# Zio_Qwiic_Gesture_Sensor_PAJ7620U2.net
KiCad netlist of a schematic drawn in EAGLE
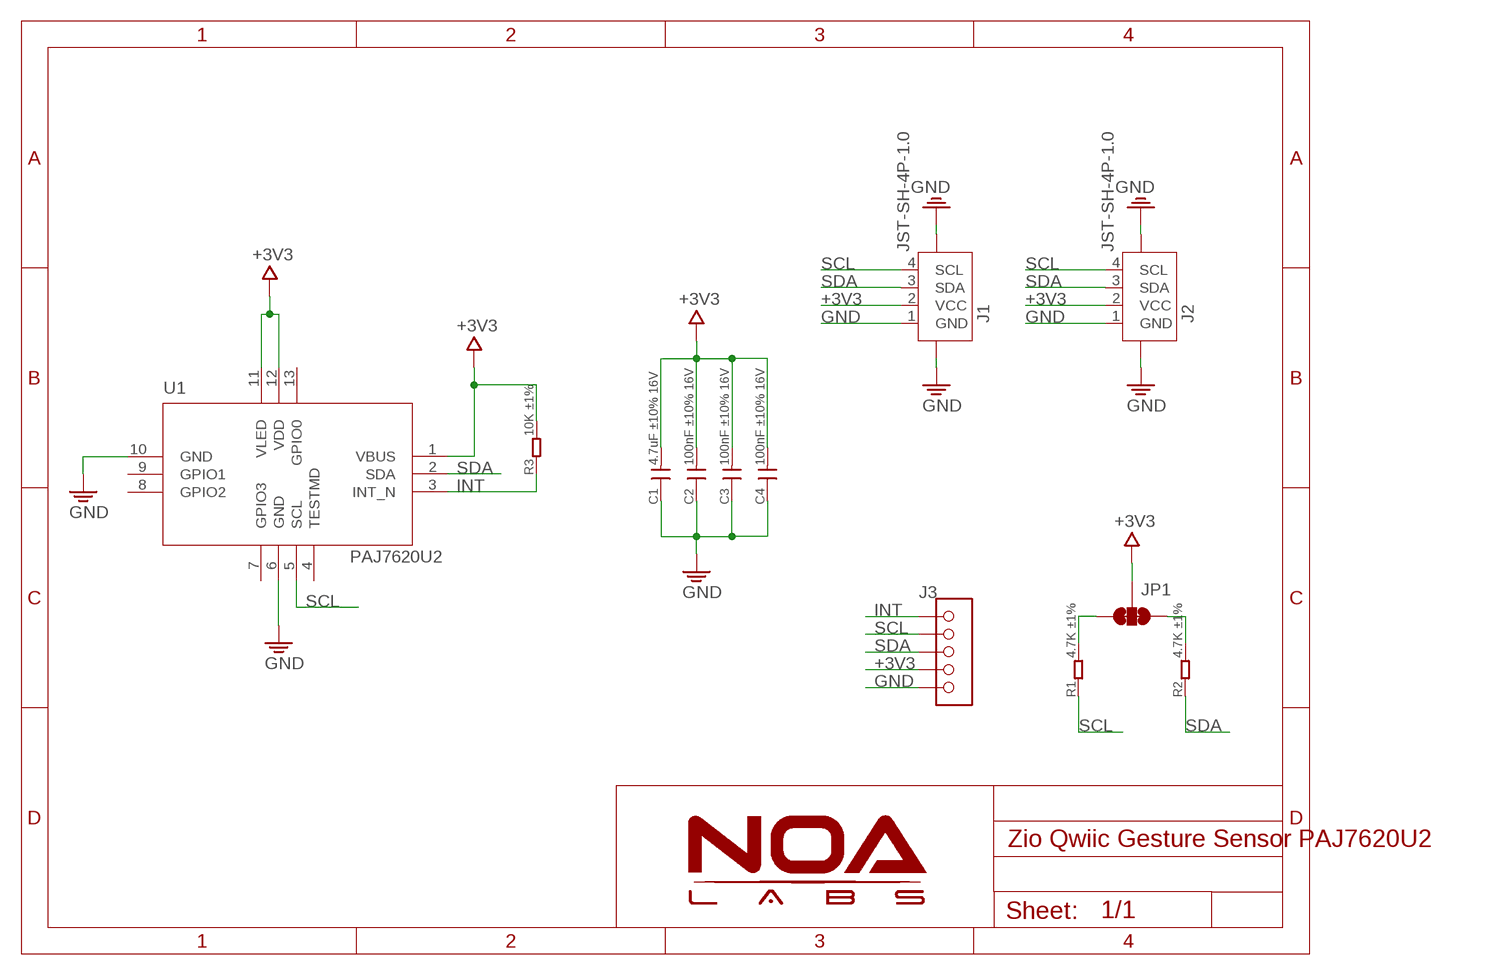
[diagram p0: schematic, sheet 1]

(export (version "E")
  (design (tool "Eeschema 10.0.6"))
  (components
    (comp (ref "C1")
      (value "4.7uF ±10% 16V")
      (footprint "eagle-import:C0603")
      (libsource (lib "eagle-import") (part "C-0603"))
    )
    (comp (ref "C2")
      (value "100nF ±10% 16V")
      (footprint "eagle-import:C0603")
      (libsource (lib "eagle-import") (part "C-0603"))
    )
    (comp (ref "C3")
      (value "100nF ±10% 16V")
      (footprint "eagle-import:C0603")
      (libsource (lib "eagle-import") (part "C-0603"))
    )
    (comp (ref "C4")
      (value "100nF ±10% 16V")
      (footprint "eagle-import:C0603")
      (libsource (lib "eagle-import") (part "C-0603"))
    )
    (comp (ref "J1")
      (value "JST-SH-4P-1.0")
      (footprint "eagle-import:JST-SH-4P")
      (libsource (lib "eagle-import") (part "JST-SH-4P-1.0"))
    )
    (comp (ref "J2")
      (value "JST-SH-4P-1.0")
      (footprint "eagle-import:JST-SH-4P")
      (libsource (lib "eagle-import") (part "JST-SH-4P-1.0"))
    )
    (comp (ref "J3")
      (value "HEADER-5P-2.54")
      (footprint "eagle-import:5P-2.54")
      (libsource (lib "eagle-import") (part "HEADER-5P-2.54"))
    )
    (comp (ref "JP1")
      (value "SMT-JUMPER_3_2-NC_TRACE")
      (footprint "eagle-import:SMT-JUMPER_3_2-NC_TRACE")
      (libsource (lib "eagle-import") (part "SMT-JUMPER_3_2-NC_TRACE"))
    )
    (comp (ref "R1")
      (value "4.7K ±1%")
      (footprint "eagle-import:R0603")
      (libsource (lib "eagle-import") (part "R-0603"))
    )
    (comp (ref "R2")
      (value "4.7K ±1%")
      (footprint "eagle-import:R0603")
      (libsource (lib "eagle-import") (part "R-0603"))
    )
    (comp (ref "R3")
      (value "10K ±1%")
      (footprint "eagle-import:R0603")
      (libsource (lib "eagle-import") (part "R-0603"))
    )
    (comp (ref "U1")
      (value "PAJ7620U2")
      (footprint "eagle-import:PAJ7620U2")
      (libsource (lib "eagle-import") (part "PAJ7620U2"))
    )
  )
  (nets
    (net (code "1") (name "+3V3") (class "Default")
      (node (ref "C1") (pin "2") (pinfunction "2_2") (pintype "passive"))
      (node (ref "C2") (pin "2") (pinfunction "2_2") (pintype "passive"))
      (node (ref "C3") (pin "2") (pinfunction "2_2") (pintype "passive"))
      (node (ref "C4") (pin "2") (pinfunction "2_2") (pintype "passive"))
      (node (ref "J1") (pin "2") (pinfunction "VCC_2") (pintype "bidirectional"))
      (node (ref "J2") (pin "2") (pinfunction "VCC_2") (pintype "bidirectional"))
      (node (ref "J3") (pin "4") (pinfunction "4_4") (pintype "bidirectional"))
      (node (ref "JP1") (pin "2") (pinfunction "2_2") (pintype "passive"))
      (node (ref "R3") (pin "2") (pinfunction "2_2") (pintype "passive"))
      (node (ref "U1") (pin "1") (pinfunction "VBUS_1") (pintype "bidirectional"))
      (node (ref "U1") (pin "11") (pinfunction "VLED_11") (pintype "bidirectional"))
      (node (ref "U1") (pin "12") (pinfunction "VDD_12") (pintype "bidirectional"))
    )
    (net (code "2") (name "/INT") (class "Default")
      (node (ref "J3") (pin "1") (pinfunction "1_1") (pintype "bidirectional"))
      (node (ref "R3") (pin "1") (pinfunction "1_1") (pintype "passive"))
      (node (ref "U1") (pin "3") (pinfunction "INT_N_3") (pintype "bidirectional"))
    )
    (net (code "3") (name "/SCL") (class "Default")
      (node (ref "J1") (pin "4") (pinfunction "SCL_4") (pintype "bidirectional"))
      (node (ref "J2") (pin "4") (pinfunction "SCL_4") (pintype "bidirectional"))
      (node (ref "J3") (pin "2") (pinfunction "2_2") (pintype "bidirectional"))
      (node (ref "R1") (pin "1") (pinfunction "1_1") (pintype "passive"))
      (node (ref "U1") (pin "5") (pinfunction "SCL_5") (pintype "bidirectional"))
    )
    (net (code "4") (name "/SDA") (class "Default")
      (node (ref "J1") (pin "3") (pinfunction "SDA_3") (pintype "bidirectional"))
      (node (ref "J2") (pin "3") (pinfunction "SDA_3") (pintype "bidirectional"))
      (node (ref "J3") (pin "3") (pinfunction "3_3") (pintype "bidirectional"))
      (node (ref "R2") (pin "1") (pinfunction "1_1") (pintype "passive"))
      (node (ref "U1") (pin "2") (pinfunction "SDA_2") (pintype "bidirectional"))
    )
    (net (code "5") (name "GND") (class "Default")
      (node (ref "C1") (pin "1") (pinfunction "1_1") (pintype "passive"))
      (node (ref "C2") (pin "1") (pinfunction "1_1") (pintype "passive"))
      (node (ref "C3") (pin "1") (pinfunction "1_1") (pintype "passive"))
      (node (ref "C4") (pin "1") (pinfunction "1_1") (pintype "passive"))
      (node (ref "J1") (pin "1") (pinfunction "GND_1") (pintype "bidirectional"))
      (node (ref "J1") (pin "NC1") (pinfunction "5_NC1") (pintype "bidirectional"))
      (node (ref "J1") (pin "NC2") (pinfunction "6_NC2") (pintype "bidirectional"))
      (node (ref "J2") (pin "1") (pinfunction "GND_1") (pintype "bidirectional"))
      (node (ref "J2") (pin "NC1") (pinfunction "5_NC1") (pintype "bidirectional"))
      (node (ref "J2") (pin "NC2") (pinfunction "6_NC2") (pintype "bidirectional"))
      (node (ref "J3") (pin "5") (pinfunction "5_5") (pintype "bidirectional"))
      (node (ref "U1") (pin "10") (pinfunction "GND_10") (pintype "bidirectional"))
      (node (ref "U1") (pin "6") (pinfunction "GND_6") (pintype "bidirectional"))
    )
    (net (code "6") (name "Net-(JP1-Pad1)") (class "Default")
      (node (ref "JP1") (pin "1") (pinfunction "1_1") (pintype "passive"))
      (node (ref "R2") (pin "2") (pinfunction "2_2") (pintype "passive"))
    )
    (net (code "7") (name "Net-(JP1-Pad3)") (class "Default")
      (node (ref "JP1") (pin "3") (pinfunction "3_3") (pintype "passive"))
      (node (ref "R1") (pin "2") (pinfunction "2_2") (pintype "passive"))
    )
    (net (code "8") (name "unconnected-(U1-GPIO0-Pad13)") (class "Default")
      (node (ref "U1") (pin "13") (pinfunction "GPIO0_13") (pintype "bidirectional"))
    )
    (net (code "9") (name "unconnected-(U1-GPIO1-Pad9)") (class "Default")
      (node (ref "U1") (pin "9") (pinfunction "GPIO1_9") (pintype "bidirectional"))
    )
    (net (code "10") (name "unconnected-(U1-GPIO2-Pad8)") (class "Default")
      (node (ref "U1") (pin "8") (pinfunction "GPIO2_8") (pintype "bidirectional"))
    )
    (net (code "11") (name "unconnected-(U1-GPIO3-Pad7)") (class "Default")
      (node (ref "U1") (pin "7") (pinfunction "GPIO3_7") (pintype "bidirectional"))
    )
    (net (code "12") (name "unconnected-(U1-TESTMD-Pad4)") (class "Default")
      (node (ref "U1") (pin "4") (pinfunction "TESTMD_4") (pintype "bidirectional"))
    )
  )
)
